# MiniPCIe.net
KiCad netlist of a schematic drawn in Altium Designer
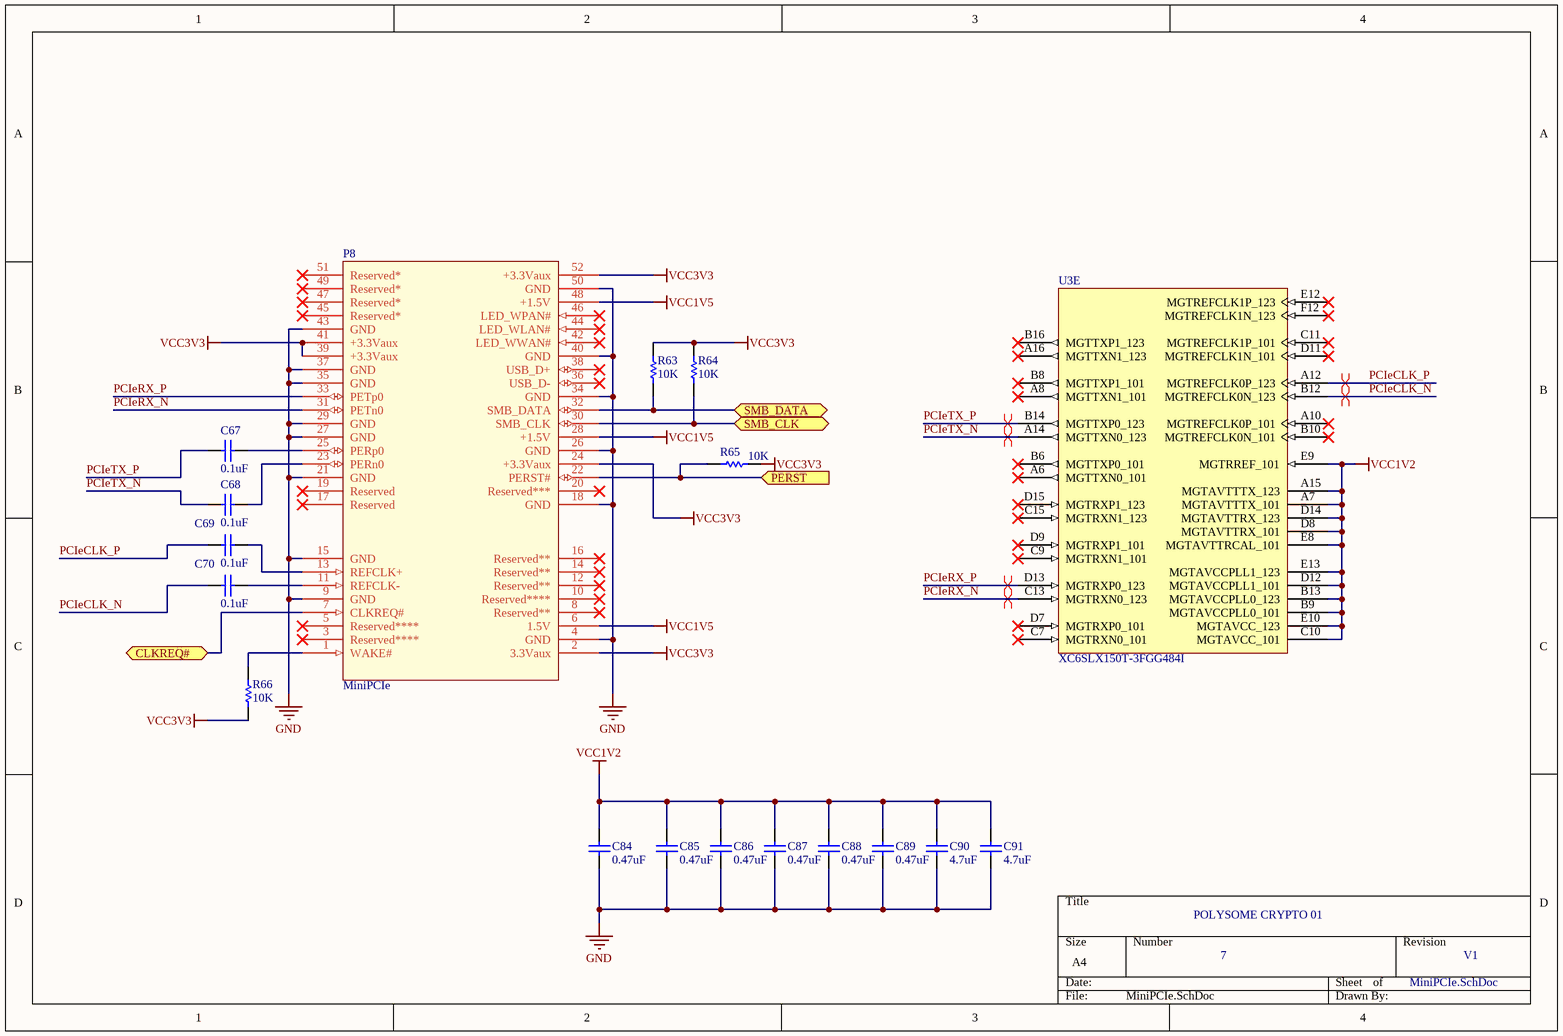
[diagram p0: MiniPCIe.SchDoc]

(export (version "E")
  (design (tool "Eeschema 10.0.6"))
  (components
    (comp (ref "C67")
      (value "0.1uF")
      (footprint "0402")
      (description "Capacitor (Semiconductor SIM Model)")
      (fields (field (name "Comment") "Cap Semi") (field (name "PUBLISHER") "Altium Limited"))
      (libsource (lib "Miscellaneous Devices") (part "Cap Semi"))
    )
    (comp (ref "C68")
      (value "0.1uF")
      (footprint "0402")
      (description "Capacitor (Semiconductor SIM Model)")
      (fields (field (name "Comment") "Cap Semi") (field (name "PUBLISHER") "Altium Limited"))
      (libsource (lib "Miscellaneous Devices") (part "Cap Semi"))
    )
    (comp (ref "C69")
      (value "0.1uF")
      (footprint "0402")
      (description "Capacitor (Semiconductor SIM Model)")
      (fields (field (name "Comment") "Cap Semi") (field (name "PUBLISHER") "Altium Limited"))
      (libsource (lib "Miscellaneous Devices") (part "Cap Semi"))
    )
    (comp (ref "C70")
      (value "0.1uF")
      (footprint "0402")
      (description "Capacitor (Semiconductor SIM Model)")
      (fields (field (name "Comment") "Cap Semi") (field (name "PUBLISHER") "Altium Limited"))
      (libsource (lib "Miscellaneous Devices") (part "Cap Semi"))
    )
    (comp (ref "C84")
      (value "0.47uF")
      (footprint "0402")
      (description "Capacitor (Semiconductor SIM Model)")
      (fields (field (name "Comment") "Cap Semi") (field (name "PUBLISHER") "Altium Limited"))
      (libsource (lib "Miscellaneous Devices") (part "Cap Semi"))
    )
    (comp (ref "C85")
      (value "0.47uF")
      (footprint "0402")
      (description "Capacitor (Semiconductor SIM Model)")
      (fields (field (name "Comment") "Cap Semi") (field (name "PUBLISHER") "Altium Limited"))
      (libsource (lib "Miscellaneous Devices") (part "Cap Semi"))
    )
    (comp (ref "C86")
      (value "0.47uF")
      (footprint "0402")
      (description "Capacitor (Semiconductor SIM Model)")
      (fields (field (name "Comment") "Cap Semi") (field (name "PUBLISHER") "Altium Limited"))
      (libsource (lib "Miscellaneous Devices") (part "Cap Semi"))
    )
    (comp (ref "C87")
      (value "0.47uF")
      (footprint "0402")
      (description "Capacitor (Semiconductor SIM Model)")
      (fields (field (name "Comment") "Cap Semi") (field (name "PUBLISHER") "Altium Limited"))
      (libsource (lib "Miscellaneous Devices") (part "Cap Semi"))
    )
    (comp (ref "C88")
      (value "0.47uF")
      (footprint "0402")
      (description "Capacitor (Semiconductor SIM Model)")
      (fields (field (name "Comment") "Cap Semi") (field (name "PUBLISHER") "Altium Limited"))
      (libsource (lib "Miscellaneous Devices") (part "Cap Semi"))
    )
    (comp (ref "C89")
      (value "0.47uF")
      (footprint "0402")
      (description "Capacitor (Semiconductor SIM Model)")
      (fields (field (name "Comment") "Cap Semi") (field (name "PUBLISHER") "Altium Limited"))
      (libsource (lib "Miscellaneous Devices") (part "Cap Semi"))
    )
    (comp (ref "C90")
      (value "4.7uF")
      (footprint "0402")
      (description "Capacitor (Semiconductor SIM Model)")
      (fields (field (name "Comment") "Cap Semi") (field (name "PUBLISHER") "Altium Limited"))
      (libsource (lib "Miscellaneous Devices") (part "Cap Semi"))
    )
    (comp (ref "C91")
      (value "4.7uF")
      (footprint "0402")
      (description "Capacitor (Semiconductor SIM Model)")
      (fields (field (name "Comment") "Cap Semi") (field (name "PUBLISHER") "Altium Limited"))
      (libsource (lib "Miscellaneous Devices") (part "Cap Semi"))
    )
    (comp (ref "P8")
      (value "MiniPCIe")
      (footprint "Mini PCI Express")
      (libsource (lib "PolySomeCrypto01") (part "MiniPCIe"))
    )
    (comp (ref "R63")
      (value "10K")
      (footprint "0402")
      (description "Semiconductor Resistor")
      (fields (field (name "Comment") "Res Semi") (field (name "PUBLISHER") "Altium Limited"))
      (libsource (lib "Miscellaneous Devices") (part "Res Semi"))
    )
    (comp (ref "R64")
      (value "10K")
      (footprint "0402")
      (description "Semiconductor Resistor")
      (fields (field (name "Comment") "Res Semi") (field (name "PUBLISHER") "Altium Limited"))
      (libsource (lib "Miscellaneous Devices") (part "Res Semi"))
    )
    (comp (ref "R65")
      (value "10K")
      (footprint "0402")
      (description "Semiconductor Resistor")
      (fields (field (name "Comment") "Res Semi") (field (name "PUBLISHER") "Altium Limited"))
      (libsource (lib "Miscellaneous Devices") (part "Res Semi"))
    )
    (comp (ref "R66")
      (value "10K")
      (footprint "0402")
      (description "Semiconductor Resistor")
      (fields (field (name "Comment") "Res Semi") (field (name "PUBLISHER") "Altium Limited"))
      (libsource (lib "Miscellaneous Devices") (part "Res Semi"))
    )
    (comp (ref "U3")
      (value "XC6SLX150T-3FGG484I")
      (footprint "FGG484")
      (fields (field (name "PUBLISHER") "Altium Limited"))
      (libsource (lib "Xilinx Spartan-6") (part "XC6SLX150T-3FGG484I"))
    )
  )
  (nets
    (net (code "1") (name "/CLKREQ#") (class "Default")
      (node (ref "P8") (pin "7") (pinfunction "CLKREQ#_7") (pintype "input"))
    )
    (net (code "2") (name "/PCIeCLK_N") (class "Default")
      (node (ref "C70") (pin "2") (pinfunction "2_2") (pintype "passive"))
      (node (ref "U3") (pin "B12") (pinfunction "MGTREFCLK0N_123_B12") (pintype "input"))
    )
    (net (code "3") (name "/PCIeCLK_P") (class "Default")
      (node (ref "C69") (pin "2") (pinfunction "2_2") (pintype "passive"))
      (node (ref "U3") (pin "A12") (pinfunction "MGTREFCLK0P_123_A12") (pintype "input"))
    )
    (net (code "4") (name "/PCIeRX_N") (class "Default")
      (node (ref "P8") (pin "31") (pinfunction "PETn0_31") (pintype "bidirectional"))
      (node (ref "U3") (pin "C13") (pinfunction "MGTRXN0_123_C13") (pintype "input"))
    )
    (net (code "5") (name "/PCIeRX_P") (class "Default")
      (node (ref "P8") (pin "33") (pinfunction "PETp0_33") (pintype "bidirectional"))
      (node (ref "U3") (pin "D13") (pinfunction "MGTRXP0_123_D13") (pintype "input"))
    )
    (net (code "6") (name "/PCIeTX_N") (class "Default")
      (node (ref "C68") (pin "2") (pinfunction "2_2") (pintype "passive"))
      (node (ref "U3") (pin "A14") (pinfunction "MGTTXN0_123_A14") (pintype "output"))
    )
    (net (code "7") (name "/PCIeTX_P") (class "Default")
      (node (ref "C67") (pin "2") (pinfunction "2_2") (pintype "passive"))
      (node (ref "U3") (pin "B14") (pinfunction "MGTTXP0_123_B14") (pintype "output"))
    )
    (net (code "8") (name "/PERST") (class "Default")
      (node (ref "P8") (pin "22") (pinfunction "PERST#_22") (pintype "bidirectional"))
      (node (ref "R65") (pin "1") (pinfunction "1_1") (pintype "passive"))
    )
    (net (code "9") (name "/SMB_CLK") (class "Default")
      (node (ref "P8") (pin "30") (pinfunction "SMB_CLK_30") (pintype "bidirectional"))
      (node (ref "R64") (pin "1") (pinfunction "1_1") (pintype "passive"))
    )
    (net (code "10") (name "/SMB_DATA") (class "Default")
      (node (ref "P8") (pin "32") (pinfunction "SMB_DATA_32") (pintype "bidirectional"))
      (node (ref "R63") (pin "1") (pinfunction "1_1") (pintype "passive"))
    )
    (net (code "11") (name "GND") (class "Default")
      (node (ref "C84") (pin "2") (pinfunction "2_2") (pintype "passive"))
      (node (ref "C85") (pin "2") (pinfunction "2_2") (pintype "passive"))
      (node (ref "C86") (pin "2") (pinfunction "2_2") (pintype "passive"))
      (node (ref "C87") (pin "2") (pinfunction "2_2") (pintype "passive"))
      (node (ref "C88") (pin "2") (pinfunction "2_2") (pintype "passive"))
      (node (ref "C89") (pin "2") (pinfunction "2_2") (pintype "passive"))
      (node (ref "C90") (pin "2") (pinfunction "2_2") (pintype "passive"))
      (node (ref "C91") (pin "2") (pinfunction "2_2") (pintype "passive"))
      (node (ref "P8") (pin "15") (pinfunction "GND_15") (pintype "power_in"))
      (node (ref "P8") (pin "18") (pinfunction "GND_18") (pintype "power_in"))
      (node (ref "P8") (pin "21") (pinfunction "GND_21") (pintype "power_in"))
      (node (ref "P8") (pin "26") (pinfunction "GND_26") (pintype "power_in"))
      (node (ref "P8") (pin "27") (pinfunction "GND_27") (pintype "power_in"))
      (node (ref "P8") (pin "29") (pinfunction "GND_29") (pintype "power_in"))
      (node (ref "P8") (pin "34") (pinfunction "GND_34") (pintype "power_in"))
      (node (ref "P8") (pin "35") (pinfunction "GND_35") (pintype "power_in"))
      (node (ref "P8") (pin "37") (pinfunction "GND_37") (pintype "power_in"))
      (node (ref "P8") (pin "4") (pinfunction "GND_4") (pintype "power_in"))
      (node (ref "P8") (pin "40") (pinfunction "GND_40") (pintype "power_in"))
      (node (ref "P8") (pin "43") (pinfunction "GND_43") (pintype "power_in"))
      (node (ref "P8") (pin "50") (pinfunction "GND_50") (pintype "power_in"))
      (node (ref "P8") (pin "9") (pinfunction "GND_9") (pintype "power_in"))
    )
    (net (code "12") (name "Net-(P8-PERn0)") (class "Default")
      (node (ref "C68") (pin "1") (pinfunction "1_1") (pintype "passive"))
      (node (ref "P8") (pin "23") (pinfunction "PERn0_23") (pintype "bidirectional"))
    )
    (net (code "13") (name "Net-(P8-PERp0)") (class "Default")
      (node (ref "C67") (pin "1") (pinfunction "1_1") (pintype "passive"))
      (node (ref "P8") (pin "25") (pinfunction "PERp0_25") (pintype "bidirectional"))
    )
    (net (code "14") (name "Net-(P8-REFCLK+)") (class "Default")
      (node (ref "C69") (pin "1") (pinfunction "1_1") (pintype "passive"))
      (node (ref "P8") (pin "13") (pinfunction "REFCLK+_13") (pintype "input"))
    )
    (net (code "15") (name "Net-(P8-REFCLK-)") (class "Default")
      (node (ref "C70") (pin "1") (pinfunction "1_1") (pintype "passive"))
      (node (ref "P8") (pin "11") (pinfunction "REFCLK-_11") (pintype "input"))
    )
    (net (code "16") (name "Net-(P8-WAKE#)") (class "Default")
      (node (ref "P8") (pin "1") (pinfunction "WAKE#_1") (pintype "input"))
      (node (ref "R66") (pin "2") (pinfunction "2_2") (pintype "passive"))
    )
    (net (code "17") (name "VCC1V2") (class "Default")
      (node (ref "C84") (pin "1") (pinfunction "1_1") (pintype "passive"))
      (node (ref "C85") (pin "1") (pinfunction "1_1") (pintype "passive"))
      (node (ref "C86") (pin "1") (pinfunction "1_1") (pintype "passive"))
      (node (ref "C87") (pin "1") (pinfunction "1_1") (pintype "passive"))
      (node (ref "C88") (pin "1") (pinfunction "1_1") (pintype "passive"))
      (node (ref "C89") (pin "1") (pinfunction "1_1") (pintype "passive"))
      (node (ref "C90") (pin "1") (pinfunction "1_1") (pintype "passive"))
      (node (ref "C91") (pin "1") (pinfunction "1_1") (pintype "passive"))
      (node (ref "U3") (pin "A15") (pinfunction "MGTAVTTTX_123_A15") (pintype "power_in"))
      (node (ref "U3") (pin "A7") (pinfunction "MGTAVTTTX_101_A7") (pintype "power_in"))
      (node (ref "U3") (pin "B13") (pinfunction "MGTAVCCPLL0_123_B13") (pintype "power_in"))
      (node (ref "U3") (pin "B9") (pinfunction "MGTAVCCPLL0_101_B9") (pintype "power_in"))
      (node (ref "U3") (pin "C10") (pinfunction "MGTAVCC_101_C10") (pintype "power_in"))
      (node (ref "U3") (pin "D12") (pinfunction "MGTAVCCPLL1_101_D12") (pintype "power_in"))
      (node (ref "U3") (pin "D14") (pinfunction "MGTAVTTRX_123_D14") (pintype "power_in"))
      (node (ref "U3") (pin "D8") (pinfunction "MGTAVTTRX_101_D8") (pintype "power_in"))
      (node (ref "U3") (pin "E10") (pinfunction "MGTAVCC_123_E10") (pintype "power_in"))
      (node (ref "U3") (pin "E13") (pinfunction "MGTAVCCPLL1_123_E13") (pintype "power_in"))
      (node (ref "U3") (pin "E8") (pinfunction "MGTAVTTRCAL_101_E8") (pintype "power_in"))
      (node (ref "U3") (pin "E9") (pinfunction "MGTRREF_101_E9") (pintype "input"))
    )
    (net (code "18") (name "VCC1V5") (class "Default")
      (node (ref "P8") (pin "28") (pinfunction "+1.5V_28") (pintype "power_in"))
      (node (ref "P8") (pin "48") (pinfunction "+1.5V_48") (pintype "power_in"))
      (node (ref "P8") (pin "6") (pinfunction "1.5V_6") (pintype "power_in"))
    )
    (net (code "19") (name "VCC3V3") (class "Default")
      (node (ref "P8") (pin "2") (pinfunction "3.3Vaux_2") (pintype "power_in"))
      (node (ref "P8") (pin "24") (pinfunction "+3.3Vaux_24") (pintype "power_in"))
      (node (ref "P8") (pin "39") (pinfunction "+3.3Vaux_39") (pintype "power_in"))
      (node (ref "P8") (pin "41") (pinfunction "+3.3Vaux_41") (pintype "power_in"))
      (node (ref "P8") (pin "52") (pinfunction "+3.3Vaux_52") (pintype "power_in"))
      (node (ref "R63") (pin "2") (pinfunction "2_2") (pintype "passive"))
      (node (ref "R64") (pin "2") (pinfunction "2_2") (pintype "passive"))
      (node (ref "R65") (pin "2") (pinfunction "2_2") (pintype "passive"))
      (node (ref "R66") (pin "1") (pinfunction "1_1") (pintype "passive"))
    )
    (net (code "20") (name "unconnected-(P8-LED_WLAN#-Pad44)") (class "Default")
      (node (ref "P8") (pin "44") (pinfunction "LED_WLAN#_44") (pintype "input+no_connect"))
    )
    (net (code "21") (name "unconnected-(P8-LED_WPAN#-Pad46)") (class "Default")
      (node (ref "P8") (pin "46") (pinfunction "LED_WPAN#_46") (pintype "input+no_connect"))
    )
    (net (code "22") (name "unconnected-(P8-LED_WWAN#-Pad42)") (class "Default")
      (node (ref "P8") (pin "42") (pinfunction "LED_WWAN#_42") (pintype "input+no_connect"))
    )
    (net (code "23") (name "unconnected-(P8-Reserved****-Pad3)") (class "Default")
      (node (ref "P8") (pin "3") (pinfunction "Reserved****_3") (pintype "tri_state+no_connect"))
    )
    (net (code "24") (name "unconnected-(P8-Reserved****-Pad5)") (class "Default")
      (node (ref "P8") (pin "5") (pinfunction "Reserved****_5") (pintype "tri_state+no_connect"))
    )
    (net (code "25") (name "unconnected-(P8-Reserved****-Pad10)") (class "Default")
      (node (ref "P8") (pin "10") (pinfunction "Reserved****_10") (pintype "tri_state+no_connect"))
    )
    (net (code "26") (name "unconnected-(P8-Reserved***-Pad20)") (class "Default")
      (node (ref "P8") (pin "20") (pinfunction "Reserved***_20") (pintype "tri_state+no_connect"))
    )
    (net (code "27") (name "unconnected-(P8-Reserved**-Pad8)") (class "Default")
      (node (ref "P8") (pin "8") (pinfunction "Reserved**_8") (pintype "tri_state+no_connect"))
    )
    (net (code "28") (name "unconnected-(P8-Reserved**-Pad12)") (class "Default")
      (node (ref "P8") (pin "12") (pinfunction "Reserved**_12") (pintype "tri_state+no_connect"))
    )
    (net (code "29") (name "unconnected-(P8-Reserved**-Pad14)") (class "Default")
      (node (ref "P8") (pin "14") (pinfunction "Reserved**_14") (pintype "tri_state+no_connect"))
    )
    (net (code "30") (name "unconnected-(P8-Reserved**-Pad16)") (class "Default")
      (node (ref "P8") (pin "16") (pinfunction "Reserved**_16") (pintype "tri_state+no_connect"))
    )
    (net (code "31") (name "unconnected-(P8-Reserved*-Pad45)") (class "Default")
      (node (ref "P8") (pin "45") (pinfunction "Reserved*_45") (pintype "tri_state+no_connect"))
    )
    (net (code "32") (name "unconnected-(P8-Reserved*-Pad47)") (class "Default")
      (node (ref "P8") (pin "47") (pinfunction "Reserved*_47") (pintype "tri_state+no_connect"))
    )
    (net (code "33") (name "unconnected-(P8-Reserved*-Pad49)") (class "Default")
      (node (ref "P8") (pin "49") (pinfunction "Reserved*_49") (pintype "tri_state+no_connect"))
    )
    (net (code "34") (name "unconnected-(P8-Reserved*-Pad51)") (class "Default")
      (node (ref "P8") (pin "51") (pinfunction "Reserved*_51") (pintype "power_in+no_connect"))
    )
    (net (code "35") (name "unconnected-(P8-Reserved-Pad17)") (class "Default")
      (node (ref "P8") (pin "17") (pinfunction "Reserved_17") (pintype "tri_state+no_connect"))
    )
    (net (code "36") (name "unconnected-(P8-Reserved-Pad19)") (class "Default")
      (node (ref "P8") (pin "19") (pinfunction "Reserved_19") (pintype "tri_state+no_connect"))
    )
    (net (code "37") (name "unconnected-(P8-USB_D+-Pad38)") (class "Default")
      (node (ref "P8") (pin "38") (pinfunction "USB_D+_38") (pintype "bidirectional+no_connect"))
    )
    (net (code "38") (name "unconnected-(P8-USB_D--Pad36)") (class "Default")
      (node (ref "P8") (pin "36") (pinfunction "USB_D-_36") (pintype "bidirectional+no_connect"))
    )
    (net (code "39") (name "unconnected-(U3E-MGTREFCLK0N_101-PadB10)") (class "Default")
      (node (ref "U3") (pin "B10") (pinfunction "MGTREFCLK0N_101_B10") (pintype "input+no_connect"))
    )
    (net (code "40") (name "unconnected-(U3E-MGTREFCLK0P_101-PadA10)") (class "Default")
      (node (ref "U3") (pin "A10") (pinfunction "MGTREFCLK0P_101_A10") (pintype "input+no_connect"))
    )
    (net (code "41") (name "unconnected-(U3E-MGTREFCLK1N_101-PadD11)") (class "Default")
      (node (ref "U3") (pin "D11") (pinfunction "MGTREFCLK1N_101_D11") (pintype "input+no_connect"))
    )
    (net (code "42") (name "unconnected-(U3E-MGTREFCLK1N_123-PadF12)") (class "Default")
      (node (ref "U3") (pin "F12") (pinfunction "MGTREFCLK1N_123_F12") (pintype "input+no_connect"))
    )
    (net (code "43") (name "unconnected-(U3E-MGTREFCLK1P_101-PadC11)") (class "Default")
      (node (ref "U3") (pin "C11") (pinfunction "MGTREFCLK1P_101_C11") (pintype "input+no_connect"))
    )
    (net (code "44") (name "unconnected-(U3E-MGTREFCLK1P_123-PadE12)") (class "Default")
      (node (ref "U3") (pin "E12") (pinfunction "MGTREFCLK1P_123_E12") (pintype "input+no_connect"))
    )
    (net (code "45") (name "unconnected-(U3E-MGTRXN0_101-PadC7)") (class "Default")
      (node (ref "U3") (pin "C7") (pinfunction "MGTRXN0_101_C7") (pintype "input+no_connect"))
    )
    (net (code "46") (name "unconnected-(U3E-MGTRXN1_101-PadC9)") (class "Default")
      (node (ref "U3") (pin "C9") (pinfunction "MGTRXN1_101_C9") (pintype "input+no_connect"))
    )
    (net (code "47") (name "unconnected-(U3E-MGTRXN1_123-PadC15)") (class "Default")
      (node (ref "U3") (pin "C15") (pinfunction "MGTRXN1_123_C15") (pintype "input+no_connect"))
    )
    (net (code "48") (name "unconnected-(U3E-MGTRXP0_101-PadD7)") (class "Default")
      (node (ref "U3") (pin "D7") (pinfunction "MGTRXP0_101_D7") (pintype "input+no_connect"))
    )
    (net (code "49") (name "unconnected-(U3E-MGTRXP1_101-PadD9)") (class "Default")
      (node (ref "U3") (pin "D9") (pinfunction "MGTRXP1_101_D9") (pintype "input+no_connect"))
    )
    (net (code "50") (name "unconnected-(U3E-MGTRXP1_123-PadD15)") (class "Default")
      (node (ref "U3") (pin "D15") (pinfunction "MGTRXP1_123_D15") (pintype "input+no_connect"))
    )
    (net (code "51") (name "unconnected-(U3E-MGTTXN0_101-PadA6)") (class "Default")
      (node (ref "U3") (pin "A6") (pinfunction "MGTTXN0_101_A6") (pintype "output+no_connect"))
    )
    (net (code "52") (name "unconnected-(U3E-MGTTXN1_101-PadA8)") (class "Default")
      (node (ref "U3") (pin "A8") (pinfunction "MGTTXN1_101_A8") (pintype "output+no_connect"))
    )
    (net (code "53") (name "unconnected-(U3E-MGTTXN1_123-PadA16)") (class "Default")
      (node (ref "U3") (pin "A16") (pinfunction "MGTTXN1_123_A16") (pintype "output+no_connect"))
    )
    (net (code "54") (name "unconnected-(U3E-MGTTXP0_101-PadB6)") (class "Default")
      (node (ref "U3") (pin "B6") (pinfunction "MGTTXP0_101_B6") (pintype "output+no_connect"))
    )
    (net (code "55") (name "unconnected-(U3E-MGTTXP1_101-PadB8)") (class "Default")
      (node (ref "U3") (pin "B8") (pinfunction "MGTTXP1_101_B8") (pintype "output+no_connect"))
    )
    (net (code "56") (name "unconnected-(U3E-MGTTXP1_123-PadB16)") (class "Default")
      (node (ref "U3") (pin "B16") (pinfunction "MGTTXP1_123_B16") (pintype "output+no_connect"))
    )
  )
)
